# POWER.net
KiCad netlist of a schematic drawn in Altium Designer
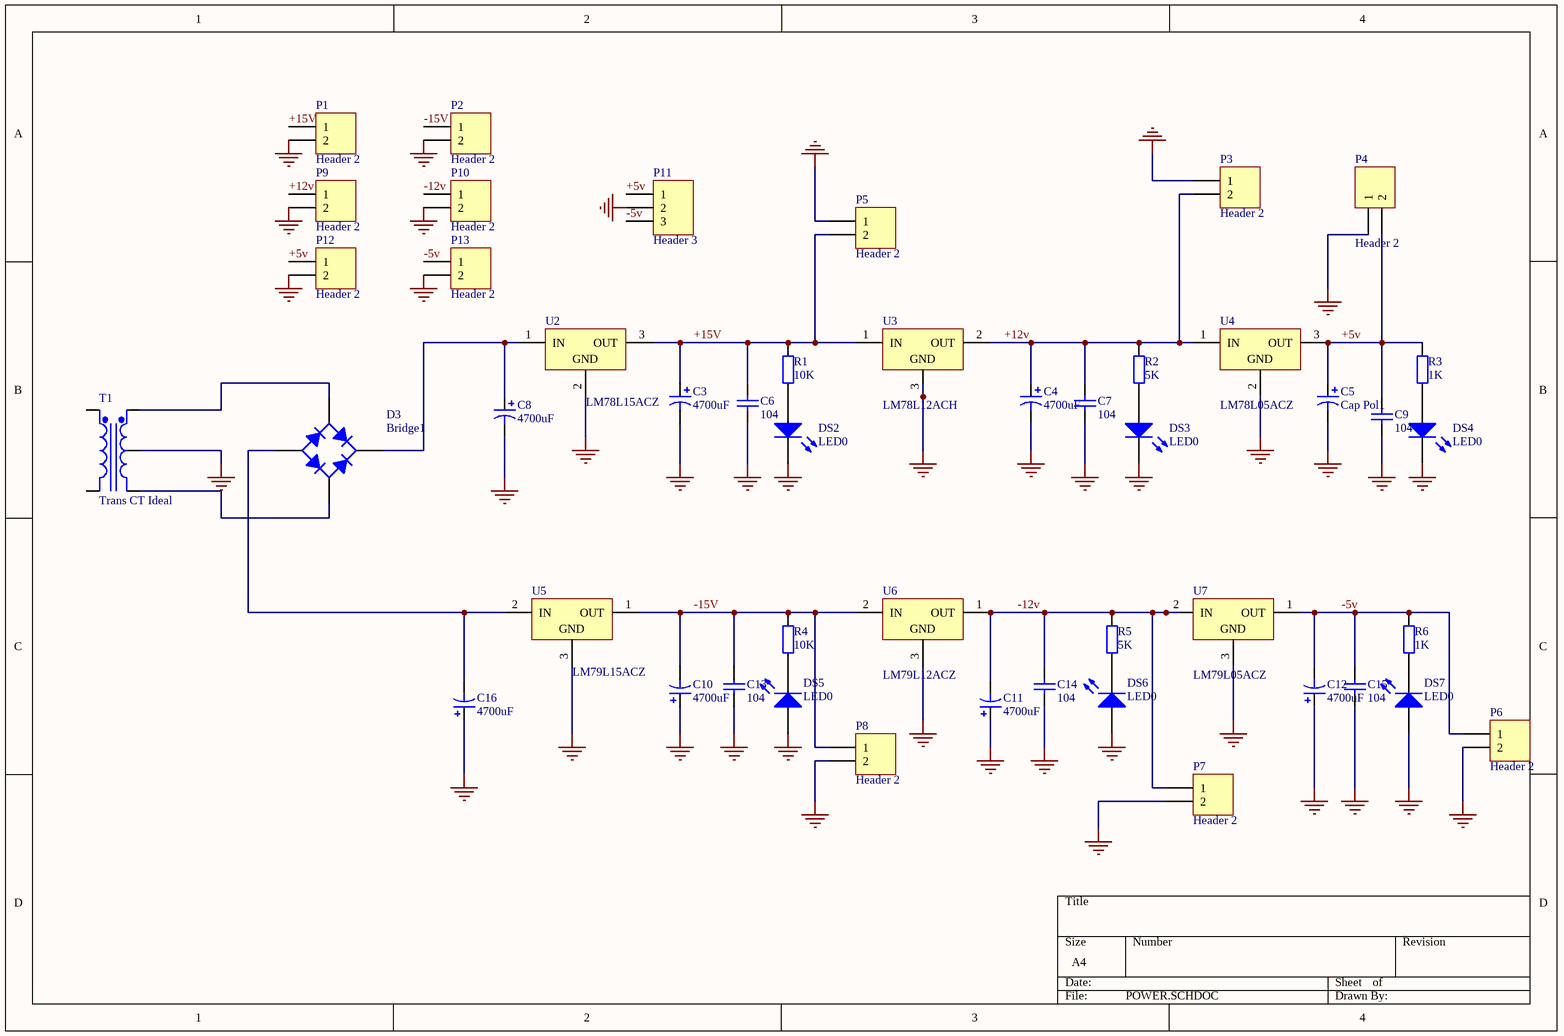
[diagram p0: POWER.SCHDOC]

(export (version "E")
  (design (tool "Eeschema 10.0.6"))
  (components
    (comp (ref "C3")
      (value "4700uF")
      (footprint "RB7.6-15")
      (description "Polarized Capacitor (Radial)")
      (fields (field (name "PUBLISHER") "Altium Limited"))
      (libsource (lib "Miscellaneous Devices") (part "Cap Pol1"))
    )
    (comp (ref "C4")
      (value "4700uF")
      (footprint "RB7.6-15")
      (description "Polarized Capacitor (Radial)")
      (fields (field (name "PUBLISHER") "Altium Limited"))
      (libsource (lib "Miscellaneous Devices") (part "Cap Pol1"))
    )
    (comp (ref "C5")
      (value "Cap Pol1")
      (footprint "RB7.6-15")
      (description "Polarized Capacitor (Radial)")
      (fields (field (name "PUBLISHER") "Altium Limited"))
      (libsource (lib "Miscellaneous Devices") (part "Cap Pol1"))
    )
    (comp (ref "C6")
      (value "104")
      (footprint "CAPR5.08-7.8x3.2")
      (description "Capacitor")
      (fields (field (name "PUBLISHER") "Altium Limited"))
      (libsource (lib "Miscellaneous Devices") (part "Cap"))
    )
    (comp (ref "C7")
      (value "104")
      (footprint "CAPR5.08-7.8x3.2")
      (description "Capacitor")
      (fields (field (name "PUBLISHER") "Altium Limited"))
      (libsource (lib "Miscellaneous Devices") (part "Cap"))
    )
    (comp (ref "C8")
      (value "4700uF")
      (footprint "RB7.6-15")
      (description "Polarized Capacitor (Radial)")
      (fields (field (name "PUBLISHER") "Altium Limited"))
      (libsource (lib "Miscellaneous Devices") (part "Cap Pol1"))
    )
    (comp (ref "C9")
      (value "104")
      (footprint "CAPR5.08-7.8x3.2")
      (description "Capacitor")
      (fields (field (name "PUBLISHER") "Altium Limited"))
      (libsource (lib "Miscellaneous Devices") (part "Cap"))
    )
    (comp (ref "C10")
      (value "4700uF")
      (footprint "RB7.6-15")
      (description "Polarized Capacitor (Radial)")
      (fields (field (name "PUBLISHER") "Altium Limited"))
      (libsource (lib "Miscellaneous Devices") (part "Cap Pol1"))
    )
    (comp (ref "C11")
      (value "4700uF")
      (footprint "RB7.6-15")
      (description "Polarized Capacitor (Radial)")
      (fields (field (name "PUBLISHER") "Altium Limited"))
      (libsource (lib "Miscellaneous Devices") (part "Cap Pol1"))
    )
    (comp (ref "C12")
      (value "4700uF")
      (footprint "RB7.6-15")
      (description "Polarized Capacitor (Radial)")
      (fields (field (name "PUBLISHER") "Altium Limited"))
      (libsource (lib "Miscellaneous Devices") (part "Cap Pol1"))
    )
    (comp (ref "C13")
      (value "104")
      (footprint "CAPR5.08-7.8x3.2")
      (description "Capacitor")
      (fields (field (name "PUBLISHER") "Altium Limited"))
      (libsource (lib "Miscellaneous Devices") (part "Cap"))
    )
    (comp (ref "C14")
      (value "104")
      (footprint "CAPR5.08-7.8x3.2")
      (description "Capacitor")
      (fields (field (name "PUBLISHER") "Altium Limited"))
      (libsource (lib "Miscellaneous Devices") (part "Cap"))
    )
    (comp (ref "C15")
      (value "104")
      (footprint "CAPR5.08-7.8x3.2")
      (description "Capacitor")
      (fields (field (name "PUBLISHER") "Altium Limited"))
      (libsource (lib "Miscellaneous Devices") (part "Cap"))
    )
    (comp (ref "C16")
      (value "4700uF")
      (footprint "RB7.6-15")
      (description "Polarized Capacitor (Radial)")
      (fields (field (name "PUBLISHER") "Altium Limited"))
      (libsource (lib "Miscellaneous Devices") (part "Cap Pol1"))
    )
    (comp (ref "D3")
      (value "Bridge1")
      (footprint "E-BIP-P4/D10")
      (description "Full Wave Diode Bridge")
      (fields (field (name "PUBLISHER") "Altium Limited"))
      (libsource (lib "Miscellaneous Devices") (part "Bridge1"))
    )
    (comp (ref "DS2")
      (value "LED0")
      (footprint "PIN2")
      (description "Typical INFRARED GaAs LED")
      (fields (field (name "PUBLISHER") "Altium Limited"))
      (libsource (lib "Miscellaneous Devices") (part "LED0"))
    )
    (comp (ref "DS3")
      (value "LED0")
      (footprint "PIN2")
      (description "Typical INFRARED GaAs LED")
      (fields (field (name "PUBLISHER") "Altium Limited"))
      (libsource (lib "Miscellaneous Devices") (part "LED0"))
    )
    (comp (ref "DS4")
      (value "LED0")
      (footprint "PIN2")
      (description "Typical INFRARED GaAs LED")
      (fields (field (name "PUBLISHER") "Altium Limited"))
      (libsource (lib "Miscellaneous Devices") (part "LED0"))
    )
    (comp (ref "DS5")
      (value "LED0")
      (footprint "PIN2")
      (description "Typical INFRARED GaAs LED")
      (fields (field (name "PUBLISHER") "Altium Limited"))
      (libsource (lib "Miscellaneous Devices") (part "LED0"))
    )
    (comp (ref "DS6")
      (value "LED0")
      (footprint "PIN2")
      (description "Typical INFRARED GaAs LED")
      (fields (field (name "PUBLISHER") "Altium Limited"))
      (libsource (lib "Miscellaneous Devices") (part "LED0"))
    )
    (comp (ref "DS7")
      (value "LED0")
      (footprint "PIN2")
      (description "Typical INFRARED GaAs LED")
      (fields (field (name "PUBLISHER") "Altium Limited"))
      (libsource (lib "Miscellaneous Devices") (part "LED0"))
    )
    (comp (ref "P1")
      (value "Header 2")
      (footprint "HDR1X2")
      (description "Header, 2-Pin")
      (fields (field (name "PUBLISHER") "Altium Limited"))
      (libsource (lib "Miscellaneous Connectors") (part "Header 2"))
    )
    (comp (ref "P2")
      (value "Header 2")
      (footprint "HDR1X2")
      (description "Header, 2-Pin")
      (fields (field (name "PUBLISHER") "Altium Limited"))
      (libsource (lib "Miscellaneous Connectors") (part "Header 2"))
    )
    (comp (ref "P3")
      (value "Header 2")
      (footprint "HDR1X2")
      (description "Header, 2-Pin")
      (fields (field (name "PUBLISHER") "Altium Limited"))
      (libsource (lib "Miscellaneous Connectors") (part "Header 2"))
    )
    (comp (ref "P4")
      (value "Header 2")
      (footprint "HDR1X2")
      (description "Header, 2-Pin")
      (fields (field (name "PUBLISHER") "Altium Limited"))
      (libsource (lib "") (part "Header 2_1"))
    )
    (comp (ref "P5")
      (value "Header 2")
      (footprint "HDR1X2")
      (description "Header, 2-Pin")
      (fields (field (name "PUBLISHER") "Altium Limited"))
      (libsource (lib "Miscellaneous Connectors") (part "Header 2"))
    )
    (comp (ref "P6")
      (value "Header 2")
      (footprint "HDR1X2")
      (description "Header, 2-Pin")
      (fields (field (name "PUBLISHER") "Altium Limited"))
      (libsource (lib "Miscellaneous Connectors") (part "Header 2"))
    )
    (comp (ref "P7")
      (value "Header 2")
      (footprint "HDR1X2")
      (description "Header, 2-Pin")
      (fields (field (name "PUBLISHER") "Altium Limited"))
      (libsource (lib "Miscellaneous Connectors") (part "Header 2"))
    )
    (comp (ref "P8")
      (value "Header 2")
      (footprint "HDR1X2")
      (description "Header, 2-Pin")
      (fields (field (name "PUBLISHER") "Altium Limited"))
      (libsource (lib "Miscellaneous Connectors") (part "Header 2"))
    )
    (comp (ref "P9")
      (value "Header 2")
      (footprint "HDR1X2")
      (description "Header, 2-Pin")
      (fields (field (name "PUBLISHER") "Altium Limited"))
      (libsource (lib "Miscellaneous Connectors") (part "Header 2"))
    )
    (comp (ref "P10")
      (value "Header 2")
      (footprint "HDR1X2")
      (description "Header, 2-Pin")
      (fields (field (name "PUBLISHER") "Altium Limited"))
      (libsource (lib "Miscellaneous Connectors") (part "Header 2"))
    )
    (comp (ref "P11")
      (value "Header 3")
      (footprint "HDR1X3")
      (description "Header, 3-Pin")
      (fields (field (name "PUBLISHER") "Altium Limited"))
      (libsource (lib "Miscellaneous Connectors") (part "Header 3"))
    )
    (comp (ref "P12")
      (value "Header 2")
      (footprint "HDR1X2")
      (description "Header, 2-Pin")
      (fields (field (name "PUBLISHER") "Altium Limited"))
      (libsource (lib "Miscellaneous Connectors") (part "Header 2"))
    )
    (comp (ref "P13")
      (value "Header 2")
      (footprint "HDR1X2")
      (description "Header, 2-Pin")
      (fields (field (name "PUBLISHER") "Altium Limited"))
      (libsource (lib "Miscellaneous Connectors") (part "Header 2"))
    )
    (comp (ref "R1")
      (value "10K")
      (footprint "AXIAL-0.4")
      (description "Resistor")
      (fields (field (name "PUBLISHER") "Altium Limited"))
      (libsource (lib "Miscellaneous Devices") (part "Res2"))
    )
    (comp (ref "R2")
      (value "5K")
      (footprint "AXIAL-0.4")
      (description "Resistor")
      (fields (field (name "PUBLISHER") "Altium Limited"))
      (libsource (lib "Miscellaneous Devices") (part "Res2"))
    )
    (comp (ref "R3")
      (value "1K")
      (footprint "AXIAL-0.4")
      (description "Resistor")
      (fields (field (name "PUBLISHER") "Altium Limited"))
      (libsource (lib "Miscellaneous Devices") (part "Res2"))
    )
    (comp (ref "R4")
      (value "10K")
      (footprint "AXIAL-0.4")
      (description "Resistor")
      (fields (field (name "PUBLISHER") "Altium Limited"))
      (libsource (lib "Miscellaneous Devices") (part "Res2"))
    )
    (comp (ref "R5")
      (value "5K")
      (footprint "AXIAL-0.4")
      (description "Resistor")
      (fields (field (name "PUBLISHER") "Altium Limited"))
      (libsource (lib "Miscellaneous Devices") (part "Res2"))
    )
    (comp (ref "R6")
      (value "1K")
      (footprint "AXIAL-0.4")
      (description "Resistor")
      (fields (field (name "PUBLISHER") "Altium Limited"))
      (libsource (lib "Miscellaneous Devices") (part "Res2"))
    )
    (comp (ref "T1")
      (value "Trans CT Ideal")
      (footprint "TRF_5")
      (description "Center-Tapped Transformer (Ideal)")
      (fields (field (name "PUBLISHER") "Altium Limited"))
      (libsource (lib "Miscellaneous Devices") (part "Trans CT Ideal"))
    )
    (comp (ref "U2")
      (value "LM78L15ACZ")
      (footprint "T03B")
      (description "3-Terminal Positive Regulator")
      (fields (field (name "PUBLISHER") "Altium Limited"))
      (libsource (lib "NSC Power Mgt Voltage Regulator") (part "LM78L15ACZ"))
    )
    (comp (ref "U3")
      (value "LM78L12ACH")
      (footprint "T03B")
      (description "3-Terminal Positive Regulator")
      (fields (field (name "PUBLISHER") "Altium Limited"))
      (libsource (lib "NSC Power Mgt Voltage Regulator") (part "LM78L12ACH"))
    )
    (comp (ref "U4")
      (value "LM78L05ACZ")
      (footprint "T03B")
      (description "3-Terminal Positive Regulator")
      (fields (field (name "PUBLISHER") "Altium Limited"))
      (libsource (lib "NSC Power Mgt Voltage Regulator") (part "LM78L05ACZ"))
    )
    (comp (ref "U5")
      (value "LM79L15ACZ")
      (footprint "T03B")
      (description "3-Terminal Negative Regulator")
      (fields (field (name "PUBLISHER") "Altium Limited"))
      (libsource (lib "NSC Power Mgt Voltage Regulator") (part "LM79L15ACZ"))
    )
    (comp (ref "U6")
      (value "LM79L12ACZ")
      (footprint "T03B")
      (description "3-Terminal Negative Regulator")
      (fields (field (name "PUBLISHER") "Altium Limited"))
      (libsource (lib "NSC Power Mgt Voltage Regulator") (part "LM79L12ACZ"))
    )
    (comp (ref "U7")
      (value "LM79L05ACZ")
      (footprint "T03B")
      (description "3-Terminal Negative Regulator")
      (fields (field (name "PUBLISHER") "Altium Limited"))
      (libsource (lib "NSC Power Mgt Voltage Regulator") (part "LM79L05ACZ"))
    )
  )
  (nets
    (net (code "1") (name "/+5v") (class "Default")
      (node (ref "C5") (pin "1") (pinfunction "1_1") (pintype "passive"))
      (node (ref "C9") (pin "2") (pinfunction "2_2") (pintype "passive"))
      (node (ref "P11") (pin "1") (pinfunction "1_1") (pintype "passive"))
      (node (ref "P12") (pin "1") (pinfunction "1_1") (pintype "passive"))
      (node (ref "P4") (pin "2") (pinfunction "2_2") (pintype "passive"))
      (node (ref "R3") (pin "2") (pinfunction "2_2") (pintype "passive"))
      (node (ref "U4") (pin "3") (pinfunction "OUT_3") (pintype "power_in"))
    )
    (net (code "2") (name "/+12v") (class "Default")
      (node (ref "C4") (pin "1") (pinfunction "1_1") (pintype "passive"))
      (node (ref "C7") (pin "2") (pinfunction "2_2") (pintype "passive"))
      (node (ref "P3") (pin "2") (pinfunction "2_2") (pintype "passive"))
      (node (ref "P9") (pin "1") (pinfunction "1_1") (pintype "passive"))
      (node (ref "R2") (pin "2") (pinfunction "2_2") (pintype "passive"))
      (node (ref "U3") (pin "2") (pinfunction "OUT_2") (pintype "power_in"))
      (node (ref "U4") (pin "1") (pinfunction "IN_1") (pintype "power_in"))
    )
    (net (code "3") (name "/+15V") (class "Default")
      (node (ref "C3") (pin "1") (pinfunction "1_1") (pintype "passive"))
      (node (ref "C6") (pin "2") (pinfunction "2_2") (pintype "passive"))
      (node (ref "P1") (pin "1") (pinfunction "1_1") (pintype "passive"))
      (node (ref "P5") (pin "2") (pinfunction "2_2") (pintype "passive"))
      (node (ref "R1") (pin "2") (pinfunction "2_2") (pintype "passive"))
      (node (ref "U2") (pin "3") (pinfunction "OUT_3") (pintype "power_in"))
      (node (ref "U3") (pin "1") (pinfunction "IN_1") (pintype "power_in"))
    )
    (net (code "4") (name "/-5v") (class "Default")
      (node (ref "C12") (pin "2") (pinfunction "2_2") (pintype "passive"))
      (node (ref "C15") (pin "2") (pinfunction "2_2") (pintype "passive"))
      (node (ref "P11") (pin "3") (pinfunction "3_3") (pintype "passive"))
      (node (ref "P13") (pin "1") (pinfunction "1_1") (pintype "passive"))
      (node (ref "P6") (pin "1") (pinfunction "1_1") (pintype "passive"))
      (node (ref "R6") (pin "2") (pinfunction "2_2") (pintype "passive"))
      (node (ref "U7") (pin "1") (pinfunction "OUT_1") (pintype "power_in"))
    )
    (net (code "5") (name "/-12v") (class "Default")
      (node (ref "C11") (pin "2") (pinfunction "2_2") (pintype "passive"))
      (node (ref "C14") (pin "2") (pinfunction "2_2") (pintype "passive"))
      (node (ref "P10") (pin "1") (pinfunction "1_1") (pintype "passive"))
      (node (ref "P7") (pin "1") (pinfunction "1_1") (pintype "passive"))
      (node (ref "R5") (pin "2") (pinfunction "2_2") (pintype "passive"))
      (node (ref "U6") (pin "1") (pinfunction "OUT_1") (pintype "power_in"))
      (node (ref "U7") (pin "2") (pinfunction "IN_2") (pintype "power_in"))
    )
    (net (code "6") (name "/-15V") (class "Default")
      (node (ref "C10") (pin "2") (pinfunction "2_2") (pintype "passive"))
      (node (ref "C13") (pin "2") (pinfunction "2_2") (pintype "passive"))
      (node (ref "P2") (pin "1") (pinfunction "1_1") (pintype "passive"))
      (node (ref "P8") (pin "1") (pinfunction "1_1") (pintype "passive"))
      (node (ref "R4") (pin "2") (pinfunction "2_2") (pintype "passive"))
      (node (ref "U5") (pin "1") (pinfunction "OUT_1") (pintype "power_in"))
      (node (ref "U6") (pin "2") (pinfunction "IN_2") (pintype "power_in"))
    )
    (net (code "7") (name "GND") (class "Default")
      (node (ref "C10") (pin "1") (pinfunction "1_1") (pintype "passive"))
      (node (ref "C11") (pin "1") (pinfunction "1_1") (pintype "passive"))
      (node (ref "C12") (pin "1") (pinfunction "1_1") (pintype "passive"))
      (node (ref "C13") (pin "1") (pinfunction "1_1") (pintype "passive"))
      (node (ref "C14") (pin "1") (pinfunction "1_1") (pintype "passive"))
      (node (ref "C15") (pin "1") (pinfunction "1_1") (pintype "passive"))
      (node (ref "C16") (pin "1") (pinfunction "1_1") (pintype "passive"))
      (node (ref "C3") (pin "2") (pinfunction "2_2") (pintype "passive"))
      (node (ref "C4") (pin "2") (pinfunction "2_2") (pintype "passive"))
      (node (ref "C5") (pin "2") (pinfunction "2_2") (pintype "passive"))
      (node (ref "C6") (pin "1") (pinfunction "1_1") (pintype "passive"))
      (node (ref "C7") (pin "1") (pinfunction "1_1") (pintype "passive"))
      (node (ref "C8") (pin "2") (pinfunction "2_2") (pintype "passive"))
      (node (ref "C9") (pin "1") (pinfunction "1_1") (pintype "passive"))
      (node (ref "DS2") (pin "2") (pinfunction "K_2") (pintype "passive"))
      (node (ref "DS3") (pin "2") (pinfunction "K_2") (pintype "passive"))
      (node (ref "DS4") (pin "2") (pinfunction "K_2") (pintype "passive"))
      (node (ref "DS5") (pin "1") (pinfunction "A_1") (pintype "passive"))
      (node (ref "DS6") (pin "1") (pinfunction "A_1") (pintype "passive"))
      (node (ref "DS7") (pin "1") (pinfunction "A_1") (pintype "passive"))
      (node (ref "P1") (pin "2") (pinfunction "2_2") (pintype "passive"))
      (node (ref "P10") (pin "2") (pinfunction "2_2") (pintype "passive"))
      (node (ref "P11") (pin "2") (pinfunction "2_2") (pintype "passive"))
      (node (ref "P12") (pin "2") (pinfunction "2_2") (pintype "passive"))
      (node (ref "P13") (pin "2") (pinfunction "2_2") (pintype "passive"))
      (node (ref "P2") (pin "2") (pinfunction "2_2") (pintype "passive"))
      (node (ref "P3") (pin "1") (pinfunction "1_1") (pintype "passive"))
      (node (ref "P4") (pin "1") (pinfunction "1_1") (pintype "passive"))
      (node (ref "P5") (pin "1") (pinfunction "1_1") (pintype "passive"))
      (node (ref "P6") (pin "2") (pinfunction "2_2") (pintype "passive"))
      (node (ref "P7") (pin "2") (pinfunction "2_2") (pintype "passive"))
      (node (ref "P8") (pin "2") (pinfunction "2_2") (pintype "passive"))
      (node (ref "P9") (pin "2") (pinfunction "2_2") (pintype "passive"))
      (node (ref "T1") (pin "4") (pinfunction "SecCT_4") (pintype "passive"))
      (node (ref "U2") (pin "2") (pinfunction "GND_2") (pintype "power_in"))
      (node (ref "U3") (pin "3") (pinfunction "GND_3") (pintype "power_in"))
      (node (ref "U4") (pin "2") (pinfunction "GND_2") (pintype "power_in"))
      (node (ref "U5") (pin "3") (pinfunction "GND_3") (pintype "power_in"))
      (node (ref "U6") (pin "3") (pinfunction "GND_3") (pintype "power_in"))
      (node (ref "U7") (pin "3") (pinfunction "GND_3") (pintype "power_in"))
    )
    (net (code "8") (name "Net-(D3-A)") (class "Default")
      (node (ref "C16") (pin "2") (pinfunction "2_2") (pintype "passive"))
      (node (ref "D3") (pin "1") (pinfunction "A_1") (pintype "passive"))
      (node (ref "U5") (pin "2") (pinfunction "IN_2") (pintype "power_in"))
    )
    (net (code "9") (name "Net-(D3-K)") (class "Default")
      (node (ref "C8") (pin "1") (pinfunction "1_1") (pintype "passive"))
      (node (ref "D3") (pin "3") (pinfunction "K_3") (pintype "passive"))
      (node (ref "U2") (pin "1") (pinfunction "IN_1") (pintype "power_in"))
    )
    (net (code "10") (name "Net-(DS2-A)") (class "Default")
      (node (ref "DS2") (pin "1") (pinfunction "A_1") (pintype "passive"))
      (node (ref "R1") (pin "1") (pinfunction "1_1") (pintype "passive"))
    )
    (net (code "11") (name "Net-(DS3-A)") (class "Default")
      (node (ref "DS3") (pin "1") (pinfunction "A_1") (pintype "passive"))
      (node (ref "R2") (pin "1") (pinfunction "1_1") (pintype "passive"))
    )
    (net (code "12") (name "Net-(DS4-A)") (class "Default")
      (node (ref "DS4") (pin "1") (pinfunction "A_1") (pintype "passive"))
      (node (ref "R3") (pin "1") (pinfunction "1_1") (pintype "passive"))
    )
    (net (code "13") (name "Net-(DS5-K)") (class "Default")
      (node (ref "DS5") (pin "2") (pinfunction "K_2") (pintype "passive"))
      (node (ref "R4") (pin "1") (pinfunction "1_1") (pintype "passive"))
    )
    (net (code "14") (name "Net-(DS6-K)") (class "Default")
      (node (ref "DS6") (pin "2") (pinfunction "K_2") (pintype "passive"))
      (node (ref "R5") (pin "1") (pinfunction "1_1") (pintype "passive"))
    )
    (net (code "15") (name "Net-(DS7-K)") (class "Default")
      (node (ref "DS7") (pin "2") (pinfunction "K_2") (pintype "passive"))
      (node (ref "R6") (pin "1") (pinfunction "1_1") (pintype "passive"))
    )
    (net (code "16") (name "Net-(T1-Sec+)") (class "Default")
      (node (ref "D3") (pin "2") (pinfunction "C_2") (pintype "passive"))
      (node (ref "T1") (pin "3") (pinfunction "Sec+_3") (pintype "passive"))
    )
    (net (code "17") (name "Net-(T1-Sec-)") (class "Default")
      (node (ref "D3") (pin "4") (pinfunction "C_4") (pintype "passive"))
      (node (ref "T1") (pin "5") (pinfunction "Sec-_5") (pintype "passive"))
    )
    (net (code "18") (name "unconnected-(T1-Pri+-Pad1)") (class "Default")
      (node (ref "T1") (pin "1") (pinfunction "Pri+_1") (pintype "passive"))
    )
    (net (code "19") (name "unconnected-(T1-Pri--Pad2)") (class "Default")
      (node (ref "T1") (pin "2") (pinfunction "Pri-_2") (pintype "passive"))
    )
  )
)
